# Nor_Flash_QSPI.net
KiCad netlist of a schematic drawn in Altium Designer
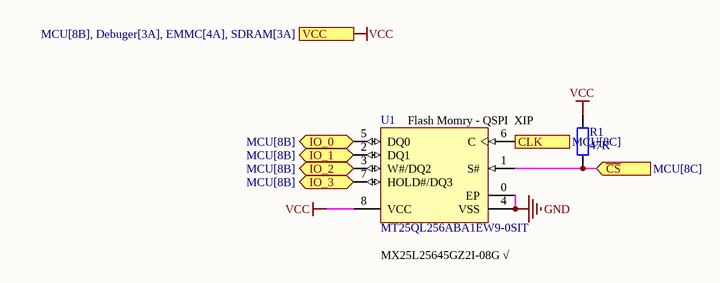
[diagram p0: Nor Flash QSPI.SchDoc]

(export (version "E")
  (design (tool "Eeschema 10.0.6"))
  (components
    (comp (ref "R1")
      (value "47K")
      (footprint "0402-R")
      (description "贴片电阻")
      (libsource (lib "0.1 - 电阻-电容-电感-晶振-晶体-磁珠-电位器") (part "R"))
    )
    (comp (ref "U1")
      (value "MT25QL256ABA1EW9-0SIT")
      (footprint "WSON8")
      (description "Micron Serial NOR Flash Memory, 2.7 to 3.6 V, 256 Mb, -40 to 85 degC, 8-Pin W-PDFN (W9), RoHS")
      (fields (field (name "MANUFACTURER") "Micron Technology"))
      (libsource (lib "MyLib") (part "MT25QL256ABA1EW9-0SIT"))
    )
  )
  (nets
    (net (code "1") (name "/CLK") (class "Default")
      (node (ref "U1") (pin "6") (pinfunction "C_6") (pintype "input"))
    )
    (net (code "2") (name "/IO_0") (class "Default")
      (node (ref "U1") (pin "5") (pinfunction "DQ0_5") (pintype "bidirectional"))
    )
    (net (code "3") (name "/IO_1") (class "Default")
      (node (ref "U1") (pin "2") (pinfunction "DQ1_2") (pintype "bidirectional"))
    )
    (net (code "4") (name "/IO_2") (class "Default")
      (node (ref "U1") (pin "3") (pinfunction "W#/DQ2_3") (pintype "bidirectional"))
    )
    (net (code "5") (name "/IO_3") (class "Default")
      (node (ref "U1") (pin "7") (pinfunction "HOLD#/DQ3_7") (pintype "bidirectional"))
    )
    (net (code "6") (name "/~{CS}") (class "Default")
      (node (ref "R1") (pin "2") (pinfunction "2_2") (pintype "passive"))
      (node (ref "U1") (pin "1") (pinfunction "S#_1") (pintype "input"))
    )
    (net (code "7") (name "GND") (class "Default")
      (node (ref "U1") (pin "0") (pinfunction "EP_0") (pintype "passive"))
      (node (ref "U1") (pin "4") (pinfunction "VSS_4") (pintype "power_in"))
    )
    (net (code "8") (name "VCC") (class "Default")
      (node (ref "R1") (pin "1") (pinfunction "1_1") (pintype "passive"))
      (node (ref "U1") (pin "8") (pinfunction "VCC_8") (pintype "power_in"))
    )
  )
)
